# Diode.net
KiCad netlist of a schematic drawn in Altium Designer
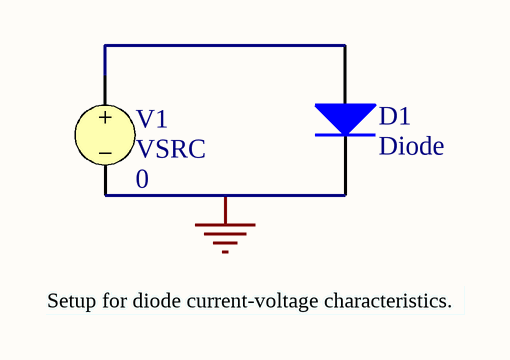
[diagram p0: Diode.SchDoc]

(export (version "E")
  (design (tool "Eeschema 10.0.6"))
  (components
    (comp (ref "D1")
      (value "Diode")
      (footprint "DSO-C2/X3.3")
      (description "Default Diode")
      (fields (field (name "PUBLISHER") "Altium Limited"))
      (libsource (lib "Miscellaneous Devices") (part "Diode"))
    )
    (comp (ref "V1")
      (value "VSRC")
      (description "Voltage Source")
      (fields (field (name "MANUFACTURER") "Generic Components") (field (name "ALTIUM_VALUE") "0"))
      (libsource (lib "Simulation Sources") (part "VSRC"))
    )
  )
  (nets
    (net (code "2") (name "GND") (class "Default")
      (node (ref "D1") (pin "2") (pinfunction "K_2") (pintype "passive"))
      (node (ref "V1") (pin "2") (pinfunction "2_2") (pintype "passive"))
    )
    (net (code "3") (name "Net-(D1-A)") (class "Default")
      (node (ref "D1") (pin "1") (pinfunction "A_1") (pintype "passive"))
      (node (ref "V1") (pin "1") (pinfunction "1_1") (pintype "passive"))
    )
  )
)
